# SCH_2-way_Traffic.net
KiCad netlist of a schematic drawn in Altium Designer
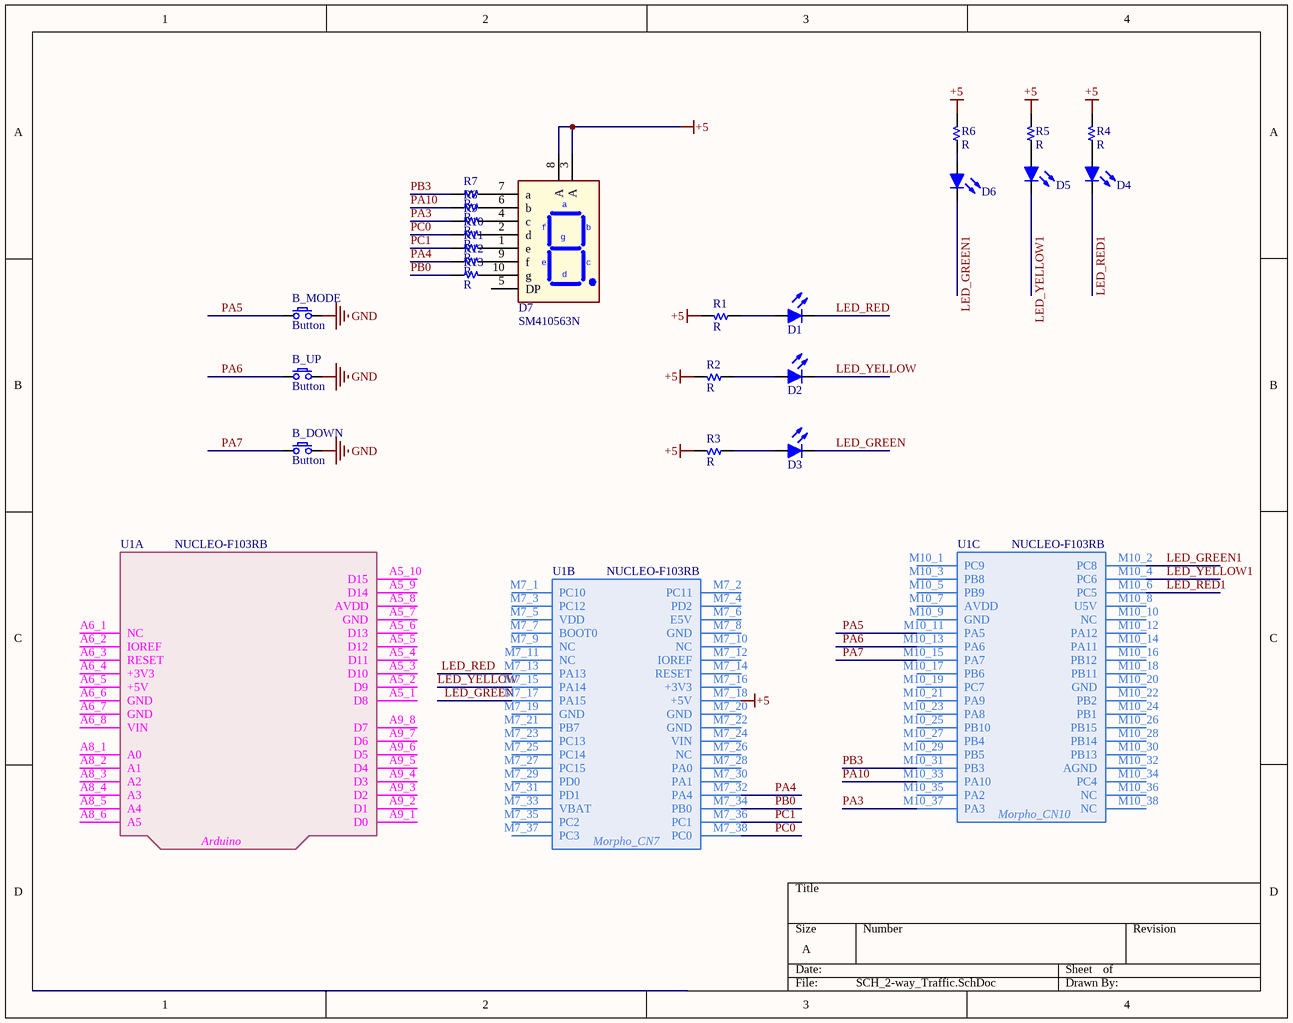
[diagram p0: SCH_2-way_Traffic.SchDoc]

(export (version "E")
  (design (tool "Eeschema 10.0.6"))
  (components
    (comp (ref "B_DOWN")
      (value "Button")
      (footprint "SW/2/DIP")
      (description "Tact switch 2 pin")
      (libsource (lib "chipfc_altium_libs") (part "SW SPST"))
    )
    (comp (ref "B_MODE")
      (value "Button")
      (footprint "SW/2/DIP")
      (description "Tact switch 2 pin")
      (libsource (lib "chipfc_altium_libs") (part "SW SPST"))
    )
    (comp (ref "B_UP")
      (value "Button")
      (footprint "SW/2/DIP")
      (description "Tact switch 2 pin")
      (libsource (lib "chipfc_altium_libs") (part "SW SPST"))
    )
    (comp (ref "D1")
      (value "Led")
      (footprint "LED 5MM - RED")
      (description "Typical LED")
      (libsource (lib "chipfc_altium_libs") (part "Led"))
    )
    (comp (ref "D2")
      (value "Led")
      (footprint "LED 5MM - WHITE")
      (description "Typical LED")
      (libsource (lib "chipfc_altium_libs") (part "Led"))
    )
    (comp (ref "D3")
      (value "Led")
      (footprint "LED 5MM - GREEN")
      (description "Typical LED")
      (libsource (lib "chipfc_altium_libs") (part "Led"))
    )
    (comp (ref "D4")
      (value "Led")
      (footprint "LED 5MM - RED")
      (description "Typical LED")
      (libsource (lib "chipfc_altium_libs") (part "Led"))
    )
    (comp (ref "D5")
      (value "Led")
      (footprint "LED 5MM - WHITE")
      (description "Typical LED")
      (libsource (lib "chipfc_altium_libs") (part "Led"))
    )
    (comp (ref "D6")
      (value "Led")
      (footprint "LED 5MM - GREEN")
      (description "Typical LED")
      (libsource (lib "chipfc_altium_libs") (part "Led"))
    )
    (comp (ref "D7")
      (value "SM410563N")
      (footprint "LED/7SEG/0.56")
      (description "SM410563N, Common-Anode, LED 7-seg, RED, 0.56\",")
      (libsource (lib "bk2022") (part "LED 7-SEG SM410563N"))
    )
    (comp (ref "R1")
      (value "R")
      (footprint "R 0805")
      (description "Resistor")
      (libsource (lib "chipfc_altium_libs") (part "Resistor"))
    )
    (comp (ref "R2")
      (value "R")
      (footprint "R 0805")
      (description "Resistor")
      (libsource (lib "chipfc_altium_libs") (part "Resistor"))
    )
    (comp (ref "R3")
      (value "R")
      (footprint "R 0805")
      (description "Resistor")
      (libsource (lib "chipfc_altium_libs") (part "Resistor"))
    )
    (comp (ref "R4")
      (value "R")
      (footprint "R 0805")
      (description "Resistor")
      (libsource (lib "chipfc_altium_libs") (part "Resistor"))
    )
    (comp (ref "R5")
      (value "R")
      (footprint "R 0805")
      (description "Resistor")
      (libsource (lib "chipfc_altium_libs") (part "Resistor"))
    )
    (comp (ref "R6")
      (value "R")
      (footprint "R 0805")
      (description "Resistor")
      (libsource (lib "chipfc_altium_libs") (part "Resistor"))
    )
    (comp (ref "R7")
      (value "R")
      (footprint "R 0805")
      (description "Resistor")
      (libsource (lib "chipfc_altium_libs") (part "Resistor"))
    )
    (comp (ref "R8")
      (value "R")
      (footprint "R 0805")
      (description "Resistor")
      (libsource (lib "chipfc_altium_libs") (part "Resistor"))
    )
    (comp (ref "R9")
      (value "R")
      (footprint "R 0805")
      (description "Resistor")
      (libsource (lib "chipfc_altium_libs") (part "Resistor"))
    )
    (comp (ref "R10")
      (value "R")
      (footprint "R 0805")
      (description "Resistor")
      (libsource (lib "chipfc_altium_libs") (part "Resistor"))
    )
    (comp (ref "R11")
      (value "R")
      (footprint "R 0805")
      (description "Resistor")
      (libsource (lib "chipfc_altium_libs") (part "Resistor"))
    )
    (comp (ref "R12")
      (value "R")
      (footprint "R 0805")
      (description "Resistor")
      (libsource (lib "chipfc_altium_libs") (part "Resistor"))
    )
    (comp (ref "R13")
      (value "R")
      (footprint "R 0805")
      (description "Resistor")
      (libsource (lib "chipfc_altium_libs") (part "Resistor"))
    )
    (comp (ref "U1")
      (value "NUCLEO-F103RB")
      (footprint "NUCLEO")
      (fields (field (name "MANUFACTURER") "STMicroelectronics"))
      (libsource (lib "nucleo") (part "NUCLEO-F103RB"))
    )
  )
  (nets
    (net (code "1") (name "+5") (class "Default")
      (node (ref "D7") (pin "3") (pinfunction "A_3") (pintype "passive"))
      (node (ref "D7") (pin "8") (pinfunction "A_8") (pintype "passive"))
      (node (ref "R1") (pin "2") (pinfunction "2_2") (pintype "passive"))
      (node (ref "R2") (pin "2") (pinfunction "2_2") (pintype "passive"))
      (node (ref "R3") (pin "2") (pinfunction "2_2") (pintype "passive"))
      (node (ref "R4") (pin "2") (pinfunction "2_2") (pintype "passive"))
      (node (ref "R5") (pin "2") (pinfunction "2_2") (pintype "passive"))
      (node (ref "R6") (pin "2") (pinfunction "2_2") (pintype "passive"))
      (node (ref "U1") (pin "M7_18") (pinfunction "+5V_M7_18") (pintype "passive"))
    )
    (net (code "2") (name "/LED_GREEN") (class "Default")
      (node (ref "D3") (pin "2") (pinfunction "K_2") (pintype "passive"))
      (node (ref "U1") (pin "M7_17") (pinfunction "PA15_M7_17") (pintype "passive"))
    )
    (net (code "3") (name "/LED_GREEN1") (class "Default")
      (node (ref "D6") (pin "2") (pinfunction "K_2") (pintype "passive"))
      (node (ref "U1") (pin "M10_2") (pinfunction "PC8_M10_2") (pintype "passive"))
    )
    (net (code "4") (name "/LED_RED") (class "Default")
      (node (ref "D1") (pin "2") (pinfunction "K_2") (pintype "passive"))
      (node (ref "U1") (pin "M7_13") (pinfunction "PA13_M7_13") (pintype "passive"))
    )
    (net (code "5") (name "/LED_RED1") (class "Default")
      (node (ref "D4") (pin "2") (pinfunction "K_2") (pintype "passive"))
      (node (ref "U1") (pin "M10_6") (pinfunction "PC5_M10_6") (pintype "passive"))
    )
    (net (code "6") (name "/LED_YELLOW") (class "Default")
      (node (ref "D2") (pin "2") (pinfunction "K_2") (pintype "passive"))
      (node (ref "U1") (pin "M7_15") (pinfunction "PA14_M7_15") (pintype "passive"))
    )
    (net (code "7") (name "/LED_YELLOW1") (class "Default")
      (node (ref "D5") (pin "2") (pinfunction "K_2") (pintype "passive"))
      (node (ref "U1") (pin "M10_4") (pinfunction "PC6_M10_4") (pintype "passive"))
    )
    (net (code "8") (name "/PA3") (class "Default")
      (node (ref "R9") (pin "1") (pinfunction "1_1") (pintype "passive"))
      (node (ref "U1") (pin "M10_37") (pinfunction "PA3_M10_37") (pintype "passive"))
    )
    (net (code "9") (name "/PA4") (class "Default")
      (node (ref "R12") (pin "1") (pinfunction "1_1") (pintype "passive"))
      (node (ref "U1") (pin "M7_32") (pinfunction "PA4_M7_32") (pintype "passive"))
    )
    (net (code "10") (name "/PA5") (class "Default")
      (node (ref "B_MODE") (pin "1") (pinfunction "1_1") (pintype "passive"))
      (node (ref "U1") (pin "M10_11") (pinfunction "PA5_M10_11") (pintype "passive"))
    )
    (net (code "11") (name "/PA6") (class "Default")
      (node (ref "B_UP") (pin "1") (pinfunction "1_1") (pintype "passive"))
      (node (ref "U1") (pin "M10_13") (pinfunction "PA6_M10_13") (pintype "passive"))
    )
    (net (code "12") (name "/PA7") (class "Default")
      (node (ref "B_DOWN") (pin "1") (pinfunction "1_1") (pintype "passive"))
      (node (ref "U1") (pin "M10_15") (pinfunction "PA7_M10_15") (pintype "passive"))
    )
    (net (code "13") (name "/PA10") (class "Default")
      (node (ref "R8") (pin "1") (pinfunction "1_1") (pintype "passive"))
      (node (ref "U1") (pin "M10_33") (pinfunction "PA10_M10_33") (pintype "passive"))
    )
    (net (code "14") (name "/PB0") (class "Default")
      (node (ref "R13") (pin "1") (pinfunction "1_1") (pintype "passive"))
      (node (ref "U1") (pin "M7_34") (pinfunction "PB0_M7_34") (pintype "passive"))
    )
    (net (code "15") (name "/PB3") (class "Default")
      (node (ref "R7") (pin "1") (pinfunction "1_1") (pintype "passive"))
      (node (ref "U1") (pin "M10_31") (pinfunction "PB3_M10_31") (pintype "passive"))
    )
    (net (code "16") (name "/PC0") (class "Default")
      (node (ref "R10") (pin "1") (pinfunction "1_1") (pintype "passive"))
      (node (ref "U1") (pin "M7_38") (pinfunction "PC0_M7_38") (pintype "passive"))
    )
    (net (code "17") (name "/PC1") (class "Default")
      (node (ref "R11") (pin "1") (pinfunction "1_1") (pintype "passive"))
      (node (ref "U1") (pin "M7_36") (pinfunction "PC1_M7_36") (pintype "passive"))
    )
    (net (code "18") (name "GND") (class "Default")
      (node (ref "B_DOWN") (pin "2") (pinfunction "2_2") (pintype "passive"))
      (node (ref "B_MODE") (pin "2") (pinfunction "2_2") (pintype "passive"))
      (node (ref "B_UP") (pin "2") (pinfunction "2_2") (pintype "passive"))
    )
    (net (code "19") (name "Net-(D1-A)") (class "Default")
      (node (ref "D1") (pin "1") (pinfunction "A_1") (pintype "passive"))
      (node (ref "R1") (pin "1") (pinfunction "1_1") (pintype "passive"))
    )
    (net (code "20") (name "Net-(D2-A)") (class "Default")
      (node (ref "D2") (pin "1") (pinfunction "A_1") (pintype "passive"))
      (node (ref "R2") (pin "1") (pinfunction "1_1") (pintype "passive"))
    )
    (net (code "21") (name "Net-(D3-A)") (class "Default")
      (node (ref "D3") (pin "1") (pinfunction "A_1") (pintype "passive"))
      (node (ref "R3") (pin "1") (pinfunction "1_1") (pintype "passive"))
    )
    (net (code "22") (name "Net-(D4-A)") (class "Default")
      (node (ref "D4") (pin "1") (pinfunction "A_1") (pintype "passive"))
      (node (ref "R4") (pin "1") (pinfunction "1_1") (pintype "passive"))
    )
    (net (code "23") (name "Net-(D5-A)") (class "Default")
      (node (ref "D5") (pin "1") (pinfunction "A_1") (pintype "passive"))
      (node (ref "R5") (pin "1") (pinfunction "1_1") (pintype "passive"))
    )
    (net (code "24") (name "Net-(D6-A)") (class "Default")
      (node (ref "D6") (pin "1") (pinfunction "A_1") (pintype "passive"))
      (node (ref "R6") (pin "1") (pinfunction "1_1") (pintype "passive"))
    )
    (net (code "25") (name "Net-(D7-a)") (class "Default")
      (node (ref "D7") (pin "7") (pinfunction "a_7") (pintype "passive"))
      (node (ref "R7") (pin "2") (pinfunction "2_2") (pintype "passive"))
    )
    (net (code "26") (name "Net-(D7-b)") (class "Default")
      (node (ref "D7") (pin "6") (pinfunction "b_6") (pintype "passive"))
      (node (ref "R8") (pin "2") (pinfunction "2_2") (pintype "passive"))
    )
    (net (code "27") (name "Net-(D7-c)") (class "Default")
      (node (ref "D7") (pin "4") (pinfunction "c_4") (pintype "passive"))
      (node (ref "R9") (pin "2") (pinfunction "2_2") (pintype "passive"))
    )
    (net (code "28") (name "Net-(D7-d)") (class "Default")
      (node (ref "D7") (pin "2") (pinfunction "d_2") (pintype "passive"))
      (node (ref "R10") (pin "2") (pinfunction "2_2") (pintype "passive"))
    )
    (net (code "29") (name "Net-(D7-e)") (class "Default")
      (node (ref "D7") (pin "1") (pinfunction "e_1") (pintype "passive"))
      (node (ref "R11") (pin "2") (pinfunction "2_2") (pintype "passive"))
    )
    (net (code "30") (name "Net-(D7-f)") (class "Default")
      (node (ref "D7") (pin "9") (pinfunction "f_9") (pintype "passive"))
      (node (ref "R12") (pin "2") (pinfunction "2_2") (pintype "passive"))
    )
    (net (code "31") (name "Net-(D7-g)") (class "Default")
      (node (ref "D7") (pin "10") (pinfunction "g_10") (pintype "passive"))
      (node (ref "R13") (pin "2") (pinfunction "2_2") (pintype "passive"))
    )
    (net (code "32") (name "unconnected-(D7-DP-Pad5)") (class "Default")
      (node (ref "D7") (pin "5") (pinfunction "DP_5") (pintype "passive"))
    )
    (net (code "33") (name "unconnected-(U1A-+3V3-PadA6_4)") (class "Default")
      (node (ref "U1") (pin "A6_4") (pinfunction "+3V3_A6_4") (pintype "passive"))
    )
    (net (code "34") (name "unconnected-(U1A-+5V-PadA6_5)") (class "Default")
      (node (ref "U1") (pin "A6_5") (pinfunction "+5V_A6_5") (pintype "passive"))
    )
    (net (code "35") (name "unconnected-(U1A-A0-PadA8_1)") (class "Default")
      (node (ref "U1") (pin "A8_1") (pinfunction "A0_A8_1") (pintype "passive"))
    )
    (net (code "36") (name "unconnected-(U1A-A1-PadA8_2)") (class "Default")
      (node (ref "U1") (pin "A8_2") (pinfunction "A1_A8_2") (pintype "passive"))
    )
    (net (code "37") (name "unconnected-(U1A-A2-PadA8_3)") (class "Default")
      (node (ref "U1") (pin "A8_3") (pinfunction "A2_A8_3") (pintype "passive"))
    )
    (net (code "38") (name "unconnected-(U1A-A3-PadA8_4)") (class "Default")
      (node (ref "U1") (pin "A8_4") (pinfunction "A3_A8_4") (pintype "passive"))
    )
    (net (code "39") (name "unconnected-(U1A-A4-PadA8_5)") (class "Default")
      (node (ref "U1") (pin "A8_5") (pinfunction "A4_A8_5") (pintype "passive"))
    )
    (net (code "40") (name "unconnected-(U1A-A5-PadA8_6)") (class "Default")
      (node (ref "U1") (pin "A8_6") (pinfunction "A5_A8_6") (pintype "passive"))
    )
    (net (code "41") (name "unconnected-(U1A-AVDD-PadA5_8)") (class "Default")
      (node (ref "U1") (pin "A5_8") (pinfunction "AVDD_A5_8") (pintype "passive"))
    )
    (net (code "42") (name "unconnected-(U1A-D0-PadA9_1)") (class "Default")
      (node (ref "U1") (pin "A9_1") (pinfunction "D0_A9_1") (pintype "passive"))
    )
    (net (code "43") (name "unconnected-(U1A-D1-PadA9_2)") (class "Default")
      (node (ref "U1") (pin "A9_2") (pinfunction "D1_A9_2") (pintype "passive"))
    )
    (net (code "44") (name "unconnected-(U1A-D2-PadA9_3)") (class "Default")
      (node (ref "U1") (pin "A9_3") (pinfunction "D2_A9_3") (pintype "passive"))
    )
    (net (code "45") (name "unconnected-(U1A-D3-PadA9_4)") (class "Default")
      (node (ref "U1") (pin "A9_4") (pinfunction "D3_A9_4") (pintype "passive"))
    )
    (net (code "46") (name "unconnected-(U1A-D4-PadA9_5)") (class "Default")
      (node (ref "U1") (pin "A9_5") (pinfunction "D4_A9_5") (pintype "passive"))
    )
    (net (code "47") (name "unconnected-(U1A-D5-PadA9_6)") (class "Default")
      (node (ref "U1") (pin "A9_6") (pinfunction "D5_A9_6") (pintype "passive"))
    )
    (net (code "48") (name "unconnected-(U1A-D6-PadA9_7)") (class "Default")
      (node (ref "U1") (pin "A9_7") (pinfunction "D6_A9_7") (pintype "passive"))
    )
    (net (code "49") (name "unconnected-(U1A-D7-PadA9_8)") (class "Default")
      (node (ref "U1") (pin "A9_8") (pinfunction "D7_A9_8") (pintype "passive"))
    )
    (net (code "50") (name "unconnected-(U1A-D8-PadA5_1)") (class "Default")
      (node (ref "U1") (pin "A5_1") (pinfunction "D8_A5_1") (pintype "passive"))
    )
    (net (code "51") (name "unconnected-(U1A-D9-PadA5_2)") (class "Default")
      (node (ref "U1") (pin "A5_2") (pinfunction "D9_A5_2") (pintype "passive"))
    )
    (net (code "52") (name "unconnected-(U1A-D10-PadA5_3)") (class "Default")
      (node (ref "U1") (pin "A5_3") (pinfunction "D10_A5_3") (pintype "passive"))
    )
    (net (code "53") (name "unconnected-(U1A-D11-PadA5_4)") (class "Default")
      (node (ref "U1") (pin "A5_4") (pinfunction "D11_A5_4") (pintype "passive"))
    )
    (net (code "54") (name "unconnected-(U1A-D12-PadA5_5)") (class "Default")
      (node (ref "U1") (pin "A5_5") (pinfunction "D12_A5_5") (pintype "passive"))
    )
    (net (code "55") (name "unconnected-(U1A-D13-PadA5_6)") (class "Default")
      (node (ref "U1") (pin "A5_6") (pinfunction "D13_A5_6") (pintype "passive"))
    )
    (net (code "56") (name "unconnected-(U1A-D14-PadA5_9)") (class "Default")
      (node (ref "U1") (pin "A5_9") (pinfunction "D14_A5_9") (pintype "passive"))
    )
    (net (code "57") (name "unconnected-(U1A-D15-PadA5_10)") (class "Default")
      (node (ref "U1") (pin "A5_10") (pinfunction "D15_A5_10") (pintype "passive"))
    )
    (net (code "58") (name "unconnected-(U1A-GND-PadA5_7)") (class "Default")
      (node (ref "U1") (pin "A5_7") (pinfunction "GND_A5_7") (pintype "passive"))
    )
    (net (code "59") (name "unconnected-(U1A-GND-PadA6_6)") (class "Default")
      (node (ref "U1") (pin "A6_6") (pinfunction "GND_A6_6") (pintype "passive"))
    )
    (net (code "60") (name "unconnected-(U1A-GND-PadA6_7)") (class "Default")
      (node (ref "U1") (pin "A6_7") (pinfunction "GND_A6_7") (pintype "passive"))
    )
    (net (code "61") (name "unconnected-(U1A-IOREF-PadA6_2)") (class "Default")
      (node (ref "U1") (pin "A6_2") (pinfunction "IOREF_A6_2") (pintype "passive"))
    )
    (net (code "62") (name "unconnected-(U1A-NC-PadA6_1)") (class "Default")
      (node (ref "U1") (pin "A6_1") (pinfunction "NC_A6_1") (pintype "passive"))
    )
    (net (code "63") (name "unconnected-(U1A-RESET-PadA6_3)") (class "Default")
      (node (ref "U1") (pin "A6_3") (pinfunction "RESET_A6_3") (pintype "passive"))
    )
    (net (code "64") (name "unconnected-(U1A-VIN-PadA6_8)") (class "Default")
      (node (ref "U1") (pin "A6_8") (pinfunction "VIN_A6_8") (pintype "passive"))
    )
    (net (code "65") (name "unconnected-(U1B-+3V3-PadM7_16)") (class "Default")
      (node (ref "U1") (pin "M7_16") (pinfunction "+3V3_M7_16") (pintype "passive"))
    )
    (net (code "66") (name "unconnected-(U1B-BOOT0-PadM7_7)") (class "Default")
      (node (ref "U1") (pin "M7_7") (pinfunction "BOOT0_M7_7") (pintype "passive"))
    )
    (net (code "67") (name "unconnected-(U1B-E5V-PadM7_6)") (class "Default")
      (node (ref "U1") (pin "M7_6") (pinfunction "E5V_M7_6") (pintype "passive"))
    )
    (net (code "68") (name "unconnected-(U1B-GND-PadM7_8)") (class "Default")
      (node (ref "U1") (pin "M7_8") (pinfunction "GND_M7_8") (pintype "passive"))
    )
    (net (code "69") (name "unconnected-(U1B-GND-PadM7_19)") (class "Default")
      (node (ref "U1") (pin "M7_19") (pinfunction "GND_M7_19") (pintype "passive"))
    )
    (net (code "70") (name "unconnected-(U1B-GND-PadM7_20)") (class "Default")
      (node (ref "U1") (pin "M7_20") (pinfunction "GND_M7_20") (pintype "passive"))
    )
    (net (code "71") (name "unconnected-(U1B-GND-PadM7_22)") (class "Default")
      (node (ref "U1") (pin "M7_22") (pinfunction "GND_M7_22") (pintype "passive"))
    )
    (net (code "72") (name "unconnected-(U1B-IOREF-PadM7_12)") (class "Default")
      (node (ref "U1") (pin "M7_12") (pinfunction "IOREF_M7_12") (pintype "passive"))
    )
    (net (code "73") (name "unconnected-(U1B-NC-PadM7_9)") (class "Default")
      (node (ref "U1") (pin "M7_9") (pinfunction "NC_M7_9") (pintype "passive"))
    )
    (net (code "74") (name "unconnected-(U1B-NC-PadM7_10)") (class "Default")
      (node (ref "U1") (pin "M7_10") (pinfunction "NC_M7_10") (pintype "passive"))
    )
    (net (code "75") (name "unconnected-(U1B-NC-PadM7_11)") (class "Default")
      (node (ref "U1") (pin "M7_11") (pinfunction "NC_M7_11") (pintype "passive"))
    )
    (net (code "76") (name "unconnected-(U1B-NC-PadM7_26)") (class "Default")
      (node (ref "U1") (pin "M7_26") (pinfunction "NC_M7_26") (pintype "passive"))
    )
    (net (code "77") (name "unconnected-(U1B-PA0-PadM7_28)") (class "Default")
      (node (ref "U1") (pin "M7_28") (pinfunction "PA0_M7_28") (pintype "passive"))
    )
    (net (code "78") (name "unconnected-(U1B-PA1-PadM7_30)") (class "Default")
      (node (ref "U1") (pin "M7_30") (pinfunction "PA1_M7_30") (pintype "passive"))
    )
    (net (code "79") (name "unconnected-(U1B-PB7-PadM7_21)") (class "Default")
      (node (ref "U1") (pin "M7_21") (pinfunction "PB7_M7_21") (pintype "passive"))
    )
    (net (code "80") (name "unconnected-(U1B-PC2-PadM7_35)") (class "Default")
      (node (ref "U1") (pin "M7_35") (pinfunction "PC2_M7_35") (pintype "passive"))
    )
    (net (code "81") (name "unconnected-(U1B-PC3-PadM7_37)") (class "Default")
      (node (ref "U1") (pin "M7_37") (pinfunction "PC3_M7_37") (pintype "passive"))
    )
    (net (code "82") (name "unconnected-(U1B-PC10-PadM7_1)") (class "Default")
      (node (ref "U1") (pin "M7_1") (pinfunction "PC10_M7_1") (pintype "passive"))
    )
    (net (code "83") (name "unconnected-(U1B-PC11-PadM7_2)") (class "Default")
      (node (ref "U1") (pin "M7_2") (pinfunction "PC11_M7_2") (pintype "passive"))
    )
    (net (code "84") (name "unconnected-(U1B-PC12-PadM7_3)") (class "Default")
      (node (ref "U1") (pin "M7_3") (pinfunction "PC12_M7_3") (pintype "passive"))
    )
    (net (code "85") (name "unconnected-(U1B-PC13-PadM7_23)") (class "Default")
      (node (ref "U1") (pin "M7_23") (pinfunction "PC13_M7_23") (pintype "passive"))
    )
    (net (code "86") (name "unconnected-(U1B-PC14-PadM7_25)") (class "Default")
      (node (ref "U1") (pin "M7_25") (pinfunction "PC14_M7_25") (pintype "passive"))
    )
    (net (code "87") (name "unconnected-(U1B-PC15-PadM7_27)") (class "Default")
      (node (ref "U1") (pin "M7_27") (pinfunction "PC15_M7_27") (pintype "passive"))
    )
    (net (code "88") (name "unconnected-(U1B-PD0-PadM7_29)") (class "Default")
      (node (ref "U1") (pin "M7_29") (pinfunction "PD0_M7_29") (pintype "passive"))
    )
    (net (code "89") (name "unconnected-(U1B-PD1-PadM7_31)") (class "Default")
      (node (ref "U1") (pin "M7_31") (pinfunction "PD1_M7_31") (pintype "passive"))
    )
    (net (code "90") (name "unconnected-(U1B-PD2-PadM7_4)") (class "Default")
      (node (ref "U1") (pin "M7_4") (pinfunction "PD2_M7_4") (pintype "passive"))
    )
    (net (code "91") (name "unconnected-(U1B-RESET-PadM7_14)") (class "Default")
      (node (ref "U1") (pin "M7_14") (pinfunction "RESET_M7_14") (pintype "passive"))
    )
    (net (code "92") (name "unconnected-(U1B-VBAT-PadM7_33)") (class "Default")
      (node (ref "U1") (pin "M7_33") (pinfunction "VBAT_M7_33") (pintype "passive"))
    )
    (net (code "93") (name "unconnected-(U1B-VDD-PadM7_5)") (class "Default")
      (node (ref "U1") (pin "M7_5") (pinfunction "VDD_M7_5") (pintype "passive"))
    )
    (net (code "94") (name "unconnected-(U1B-VIN-PadM7_24)") (class "Default")
      (node (ref "U1") (pin "M7_24") (pinfunction "VIN_M7_24") (pintype "passive"))
    )
    (net (code "95") (name "unconnected-(U1C-AGND-PadM10_32)") (class "Default")
      (node (ref "U1") (pin "M10_32") (pinfunction "AGND_M10_32") (pintype "passive"))
    )
    (net (code "96") (name "unconnected-(U1C-AVDD-PadM10_7)") (class "Default")
      (node (ref "U1") (pin "M10_7") (pinfunction "AVDD_M10_7") (pintype "passive"))
    )
    (net (code "97") (name "unconnected-(U1C-GND-PadM10_9)") (class "Default")
      (node (ref "U1") (pin "M10_9") (pinfunction "GND_M10_9") (pintype "passive"))
    )
    (net (code "98") (name "unconnected-(U1C-GND-PadM10_20)") (class "Default")
      (node (ref "U1") (pin "M10_20") (pinfunction "GND_M10_20") (pintype "passive"))
    )
    (net (code "99") (name "unconnected-(U1C-NC-PadM10_10)") (class "Default")
      (node (ref "U1") (pin "M10_10") (pinfunction "NC_M10_10") (pintype "passive"))
    )
    (net (code "100") (name "unconnected-(U1C-NC-PadM10_36)") (class "Default")
      (node (ref "U1") (pin "M10_36") (pinfunction "NC_M10_36") (pintype "passive"))
    )
    (net (code "101") (name "unconnected-(U1C-NC-PadM10_38)") (class "Default")
      (node (ref "U1") (pin "M10_38") (pinfunction "NC_M10_38") (pintype "passive"))
    )
    (net (code "102") (name "unconnected-(U1C-PA2-PadM10_35)") (class "Default")
      (node (ref "U1") (pin "M10_35") (pinfunction "PA2_M10_35") (pintype "passive"))
    )
    (net (code "103") (name "unconnected-(U1C-PA8-PadM10_23)") (class "Default")
      (node (ref "U1") (pin "M10_23") (pinfunction "PA8_M10_23") (pintype "passive"))
    )
    (net (code "104") (name "unconnected-(U1C-PA9-PadM10_21)") (class "Default")
      (node (ref "U1") (pin "M10_21") (pinfunction "PA9_M10_21") (pintype "passive"))
    )
    (net (code "105") (name "unconnected-(U1C-PA11-PadM10_14)") (class "Default")
      (node (ref "U1") (pin "M10_14") (pinfunction "PA11_M10_14") (pintype "passive"))
    )
    (net (code "106") (name "unconnected-(U1C-PA12-PadM10_12)") (class "Default")
      (node (ref "U1") (pin "M10_12") (pinfunction "PA12_M10_12") (pintype "passive"))
    )
    (net (code "107") (name "unconnected-(U1C-PB1-PadM10_24)") (class "Default")
      (node (ref "U1") (pin "M10_24") (pinfunction "PB1_M10_24") (pintype "passive"))
    )
    (net (code "108") (name "unconnected-(U1C-PB2-PadM10_22)") (class "Default")
      (node (ref "U1") (pin "M10_22") (pinfunction "PB2_M10_22") (pintype "passive"))
    )
    (net (code "109") (name "unconnected-(U1C-PB4-PadM10_27)") (class "Default")
      (node (ref "U1") (pin "M10_27") (pinfunction "PB4_M10_27") (pintype "passive"))
    )
    (net (code "110") (name "unconnected-(U1C-PB5-PadM10_29)") (class "Default")
      (node (ref "U1") (pin "M10_29") (pinfunction "PB5_M10_29") (pintype "passive"))
    )
    (net (code "111") (name "unconnected-(U1C-PB6-PadM10_17)") (class "Default")
      (node (ref "U1") (pin "M10_17") (pinfunction "PB6_M10_17") (pintype "passive"))
    )
    (net (code "112") (name "unconnected-(U1C-PB8-PadM10_3)") (class "Default")
      (node (ref "U1") (pin "M10_3") (pinfunction "PB8_M10_3") (pintype "passive"))
    )
    (net (code "113") (name "unconnected-(U1C-PB9-PadM10_5)") (class "Default")
      (node (ref "U1") (pin "M10_5") (pinfunction "PB9_M10_5") (pintype "passive"))
    )
    (net (code "114") (name "unconnected-(U1C-PB10-PadM10_25)") (class "Default")
      (node (ref "U1") (pin "M10_25") (pinfunction "PB10_M10_25") (pintype "passive"))
    )
    (net (code "115") (name "unconnected-(U1C-PB11-PadM10_18)") (class "Default")
      (node (ref "U1") (pin "M10_18") (pinfunction "PB11_M10_18") (pintype "passive"))
    )
    (net (code "116") (name "unconnected-(U1C-PB12-PadM10_16)") (class "Default")
      (node (ref "U1") (pin "M10_16") (pinfunction "PB12_M10_16") (pintype "passive"))
    )
    (net (code "117") (name "unconnected-(U1C-PB13-PadM10_30)") (class "Default")
      (node (ref "U1") (pin "M10_30") (pinfunction "PB13_M10_30") (pintype "passive"))
    )
    (net (code "118") (name "unconnected-(U1C-PB14-PadM10_28)") (class "Default")
      (node (ref "U1") (pin "M10_28") (pinfunction "PB14_M10_28") (pintype "passive"))
    )
    (net (code "119") (name "unconnected-(U1C-PB15-PadM10_26)") (class "Default")
      (node (ref "U1") (pin "M10_26") (pinfunction "PB15_M10_26") (pintype "passive"))
    )
    (net (code "120") (name "unconnected-(U1C-PC4-PadM10_34)") (class "Default")
      (node (ref "U1") (pin "M10_34") (pinfunction "PC4_M10_34") (pintype "passive"))
    )
    (net (code "121") (name "unconnected-(U1C-PC7-PadM10_19)") (class "Default")
      (node (ref "U1") (pin "M10_19") (pinfunction "PC7_M10_19") (pintype "passive"))
    )
    (net (code "122") (name "unconnected-(U1C-PC9-PadM10_1)") (class "Default")
      (node (ref "U1") (pin "M10_1") (pinfunction "PC9_M10_1") (pintype "passive"))
    )
    (net (code "123") (name "unconnected-(U1C-U5V-PadM10_8)") (class "Default")
      (node (ref "U1") (pin "M10_8") (pinfunction "U5V_M10_8") (pintype "passive"))
    )
  )
)
